# M5_Stick_LED_Chain_Module_2020-05-28_18-.net
KiCad netlist of a schematic drawn in EasyEDA
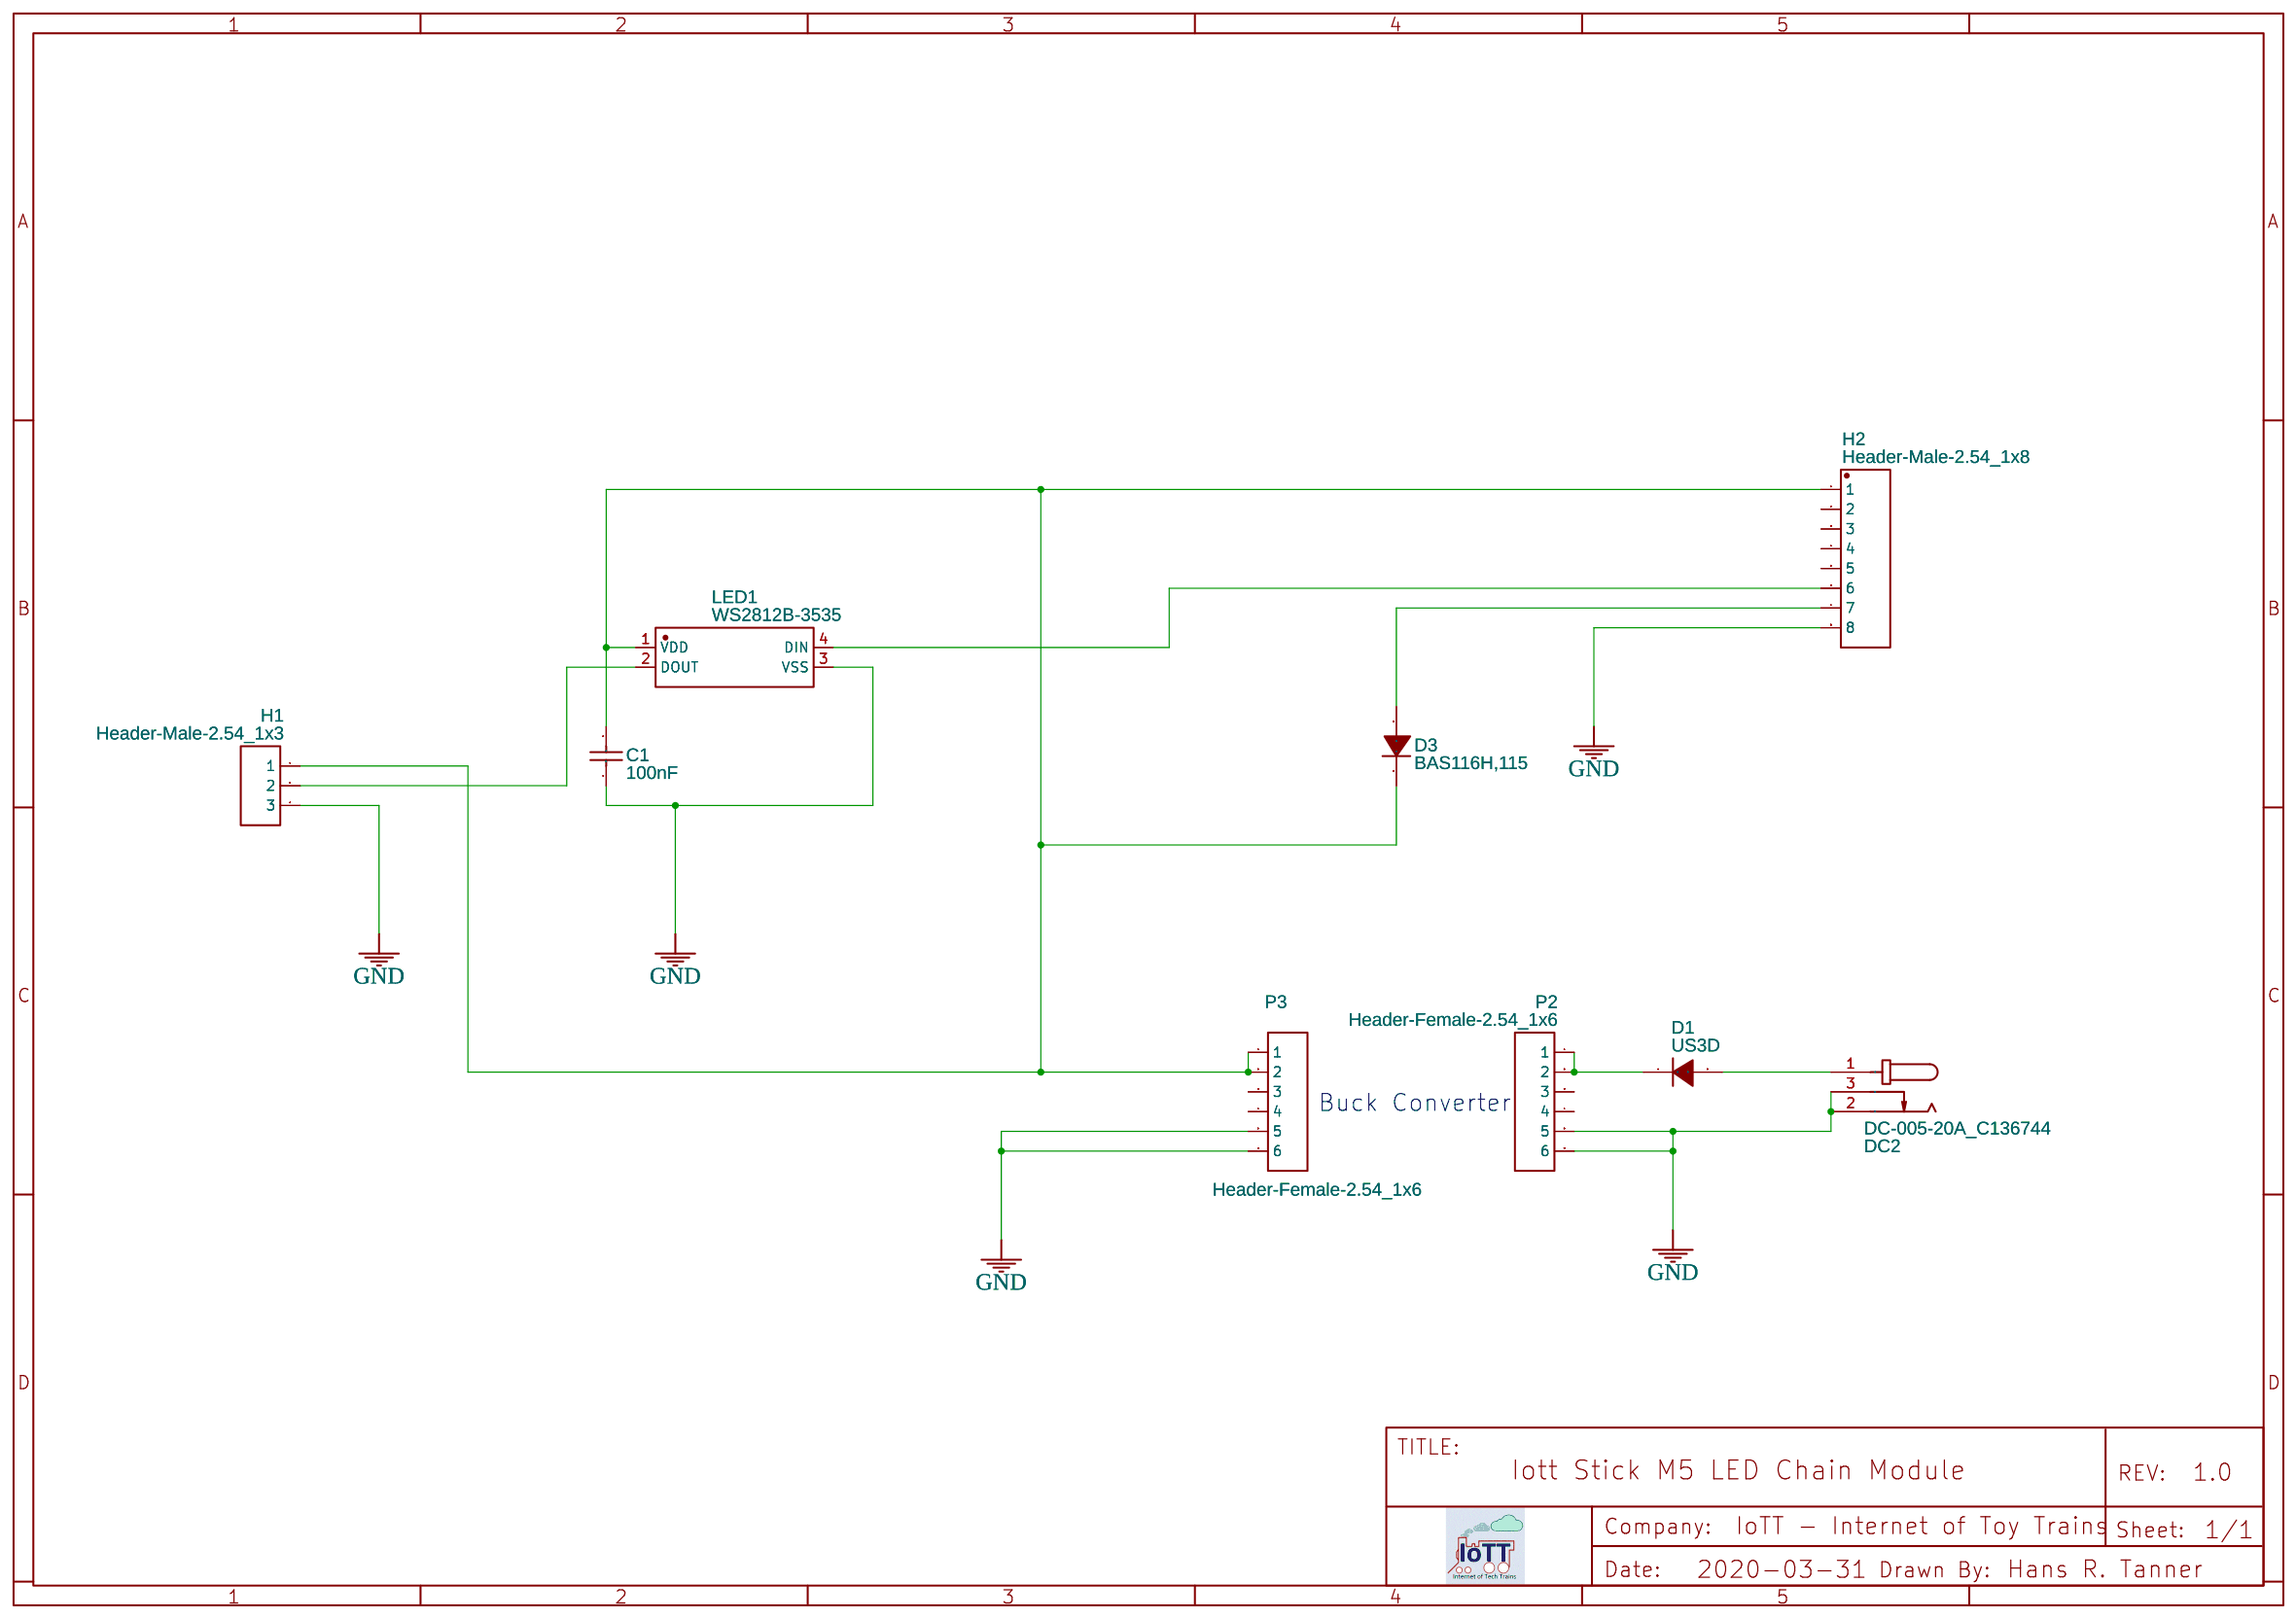
[diagram p0: schematic sheet]

(export (version "E")
  (design (tool "Eeschema 10.0.6"))
  (components
    (comp (ref "C1")
      (value "100nF")
      (fields
        (field (name "BOM_Manufacturer Part") "CL05B104KO5NNNC")
        (field (name "BOM_Supplier Part") "C1525")
      )
      (libsource (lib "") (part "CL05B104KO5NNNC"))
    )
    (comp (ref "D1")
      (value "US3D")
      (fields (field (name "BOM_Supplier Part") "C64964"))
      (libsource (lib "") (part "US3D"))
    )
    (comp (ref "D3")
      (value "BAS116H,115")
      (fields (field (name "BOM_Supplier Part") "C74210"))
      (libsource (lib "") (part "BAS116H,115"))
    )
    (comp (ref "DC2")
      (value "DC-005-20A_C136744")
      (fields
        (field (name "BOM_Manufacturer Part") "DC-005-20A")
        (field (name "BOM_Supplier Part") "C136744")
      )
      (libsource (lib "") (part "DC-005-20A_C136744"))
    )
    (comp (ref "H1")
      (value "Header-Male-2.54_1x3")
      (fields
        (field (name "BOM_Manufacturer Part") "Header2.54mm 1*3P")
        (field (name "BOM_Supplier Part") "C49257")
      )
      (libsource (lib "") (part "Header-Male-2.54_1x3"))
    )
    (comp (ref "H2")
      (value "Header-Male-2.54_1x8")
      (fields
        (field (name "BOM_Manufacturer Part") "210S-1*8P L=11.6MMGold-plated black")
        (field (name "BOM_Supplier Part") "C124381")
      )
      (libsource (lib "") (part "Header-Male-2.54_1x8"))
    )
    (comp (ref "LED1")
      (value "WS2812B-3535")
      (fields (field (name "BOM_Supplier Part") "C114583"))
      (libsource (lib "") (part "WS2812B-3535"))
    )
    (comp (ref "P2")
      (value "Header-Female-2.54_1x6")
      (fields
        (field (name "BOM_Manufacturer Part") "Female header 1*6p")
        (field (name "BOM_Supplier Part") "C40877")
      )
      (libsource (lib "") (part "Header-Female-2.54_1x6"))
    )
    (comp (ref "P3")
      (value "Header-Female-2.54_1x6")
      (fields
        (field (name "BOM_Manufacturer Part") "Female header 1*6p")
        (field (name "BOM_Supplier Part") "C40877")
      )
      (libsource (lib "") (part "Header-Female-2.54_1x6_1"))
    )
  )
  (nets
    (net (code "1") (name "GND") (class "Default")
      (node (ref "C1") (pin "1") (pinfunction "1_1") (pintype "input"))
      (node (ref "DC2") (pin "2") (pinfunction "2_2") (pintype "unspecified"))
      (node (ref "DC2") (pin "3") (pinfunction "3_3") (pintype "unspecified"))
      (node (ref "H1") (pin "3") (pinfunction "3_3") (pintype "input"))
      (node (ref "H2") (pin "8") (pinfunction "8_8") (pintype "unspecified"))
      (node (ref "LED1") (pin "3") (pinfunction "VSS_3") (pintype "unspecified"))
      (node (ref "P2") (pin "5") (pinfunction "5_5") (pintype "input"))
      (node (ref "P2") (pin "6") (pinfunction "6_6") (pintype "input"))
      (node (ref "P3") (pin "5") (pinfunction "5_5") (pintype "input"))
      (node (ref "P3") (pin "6") (pinfunction "6_6") (pintype "input"))
    )
    (net (code "2") (name "Net-(D1-Pad1)") (class "Default")
      (node (ref "D1") (pin "1") (pinfunction "1_1") (pintype "unspecified"))
      (node (ref "P2") (pin "1") (pinfunction "1_1") (pintype "input"))
      (node (ref "P2") (pin "2") (pinfunction "2_2") (pintype "input"))
    )
    (net (code "3") (name "Net-(D1-Pad2)") (class "Default")
      (node (ref "D1") (pin "2") (pinfunction "2_2") (pintype "unspecified"))
      (node (ref "DC2") (pin "1") (pinfunction "1_1") (pintype "unspecified"))
    )
    (net (code "4") (name "Net-(D3-A)") (class "Default")
      (node (ref "D3") (pin "2") (pinfunction "A_2") (pintype "unspecified"))
      (node (ref "H2") (pin "7") (pinfunction "7_7") (pintype "unspecified"))
    )
    (net (code "5") (name "Net-(D3-K)") (class "Default")
      (node (ref "C1") (pin "2") (pinfunction "2_2") (pintype "input"))
      (node (ref "D3") (pin "1") (pinfunction "K_1") (pintype "unspecified"))
      (node (ref "H1") (pin "1") (pinfunction "1_1") (pintype "input"))
      (node (ref "H2") (pin "1") (pinfunction "1_1") (pintype "unspecified"))
      (node (ref "LED1") (pin "1") (pinfunction "VDD_1") (pintype "unspecified"))
      (node (ref "P3") (pin "1") (pinfunction "1_1") (pintype "input"))
      (node (ref "P3") (pin "2") (pinfunction "2_2") (pintype "input"))
    )
    (net (code "6") (name "Net-(LED1-DIN)") (class "Default")
      (node (ref "H2") (pin "6") (pinfunction "6_6") (pintype "unspecified"))
      (node (ref "LED1") (pin "4") (pinfunction "DIN_4") (pintype "unspecified"))
    )
    (net (code "7") (name "Net-(LED1-DOUT)") (class "Default")
      (node (ref "H1") (pin "2") (pinfunction "2_2") (pintype "input"))
      (node (ref "LED1") (pin "2") (pinfunction "DOUT_2") (pintype "unspecified"))
    )
    (net (code "8") (name "unconnected-(H2-Pad2)") (class "Default")
      (node (ref "H2") (pin "2") (pinfunction "2_2") (pintype "unspecified"))
    )
    (net (code "9") (name "unconnected-(H2-Pad3)") (class "Default")
      (node (ref "H2") (pin "3") (pinfunction "3_3") (pintype "unspecified"))
    )
    (net (code "10") (name "unconnected-(H2-Pad4)") (class "Default")
      (node (ref "H2") (pin "4") (pinfunction "4_4") (pintype "unspecified"))
    )
    (net (code "11") (name "unconnected-(H2-Pad5)") (class "Default")
      (node (ref "H2") (pin "5") (pinfunction "5_5") (pintype "unspecified"))
    )
    (net (code "12") (name "unconnected-(P2-Pad3)") (class "Default")
      (node (ref "P2") (pin "3") (pinfunction "3_3") (pintype "input"))
    )
    (net (code "13") (name "unconnected-(P2-Pad4)") (class "Default")
      (node (ref "P2") (pin "4") (pinfunction "4_4") (pintype "input"))
    )
    (net (code "14") (name "unconnected-(P3-Pad3)") (class "Default")
      (node (ref "P3") (pin "3") (pinfunction "3_3") (pintype "input"))
    )
    (net (code "15") (name "unconnected-(P3-Pad4)") (class "Default")
      (node (ref "P3") (pin "4") (pinfunction "4_4") (pintype "input"))
    )
  )
)
